# bbb_connection_board.net
KiCad netlist of a schematic drawn in EAGLE
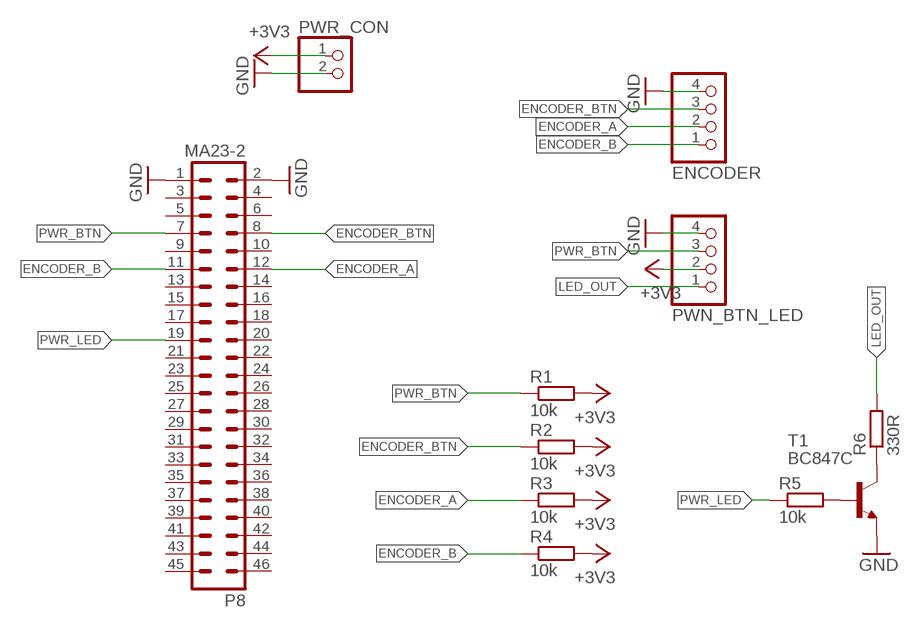
[diagram p0: schematic, sheet 1]

(export (version "E")
  (design (tool "Eeschema 10.0.6"))
  (components
    (comp (ref "ENCODER")
      (value "PINHD-1X4/90")
      (footprint "eagle-import:1X04_90")
      (libsource (lib "eagle-import") (part "PINHD-1X4/90"))
    )
    (comp (ref "P8")
      (value "MA23-2")
      (footprint "eagle-import:MA23-2")
      (libsource (lib "eagle-import") (part "MA23-2"))
    )
    (comp (ref "PWN_BTN_LED")
      (value "PINHD-1X4/90")
      (footprint "eagle-import:1X04_90")
      (libsource (lib "eagle-import") (part "PINHD-1X4/90"))
    )
    (comp (ref "PWR_CON")
      (value "PINHD-1X2/90")
      (footprint "eagle-import:1X02_90")
      (libsource (lib "eagle-import") (part "PINHD-1X2/90"))
    )
    (comp (ref "R1")
      (value "10k")
      (footprint "eagle-import:R0805")
      (libsource (lib "eagle-import") (part "R-EU_R0805"))
    )
    (comp (ref "R2")
      (value "10k")
      (footprint "eagle-import:R0805")
      (libsource (lib "eagle-import") (part "R-EU_R0805"))
    )
    (comp (ref "R3")
      (value "10k")
      (footprint "eagle-import:R0805")
      (libsource (lib "eagle-import") (part "R-EU_R0805"))
    )
    (comp (ref "R4")
      (value "10k")
      (footprint "eagle-import:R0805")
      (libsource (lib "eagle-import") (part "R-EU_R0805"))
    )
    (comp (ref "R5")
      (value "10k")
      (footprint "eagle-import:R0805")
      (libsource (lib "eagle-import") (part "R-EU_R0805"))
    )
    (comp (ref "R6")
      (value "330R")
      (footprint "eagle-import:R0805")
      (libsource (lib "eagle-import") (part "R-EU_R0805"))
    )
    (comp (ref "T1")
      (value "BC847C")
      (footprint "eagle-import:SOT23-BEC")
      (libsource (lib "eagle-import") (part "-NPN-SOT23-BECBC847A"))
    )
  )
  (nets
    (net (code "1") (name "+3V3") (class "Default")
      (node (ref "PWN_BTN_LED") (pin "2") (pinfunction "2_2") (pintype "passive"))
      (node (ref "PWR_CON") (pin "1") (pinfunction "1_1") (pintype "passive"))
      (node (ref "R1") (pin "2") (pinfunction "2_2") (pintype "passive"))
      (node (ref "R2") (pin "2") (pinfunction "2_2") (pintype "passive"))
      (node (ref "R3") (pin "2") (pinfunction "2_2") (pintype "passive"))
      (node (ref "R4") (pin "2") (pinfunction "2_2") (pintype "passive"))
    )
    (net (code "2") (name "ENCODER_A") (class "Default")
      (node (ref "ENCODER") (pin "2") (pinfunction "2_2") (pintype "passive"))
      (node (ref "P8") (pin "12") (pinfunction "12_12") (pintype "passive"))
      (node (ref "R3") (pin "1") (pinfunction "1_1") (pintype "passive"))
    )
    (net (code "3") (name "ENCODER_B") (class "Default")
      (node (ref "ENCODER") (pin "1") (pinfunction "1_1") (pintype "passive"))
      (node (ref "P8") (pin "11") (pinfunction "11_11") (pintype "passive"))
      (node (ref "R4") (pin "1") (pinfunction "1_1") (pintype "passive"))
    )
    (net (code "4") (name "ENCODER_BTN") (class "Default")
      (node (ref "ENCODER") (pin "3") (pinfunction "3_3") (pintype "passive"))
      (node (ref "P8") (pin "8") (pinfunction "8_8") (pintype "passive"))
      (node (ref "R2") (pin "1") (pinfunction "1_1") (pintype "passive"))
    )
    (net (code "5") (name "GND") (class "Default")
      (node (ref "ENCODER") (pin "4") (pinfunction "4_4") (pintype "passive"))
      (node (ref "P8") (pin "1") (pinfunction "1_1") (pintype "passive"))
      (node (ref "P8") (pin "2") (pinfunction "2_2") (pintype "passive"))
      (node (ref "PWN_BTN_LED") (pin "4") (pinfunction "4_4") (pintype "passive"))
      (node (ref "PWR_CON") (pin "2") (pinfunction "2_2") (pintype "passive"))
      (node (ref "T1") (pin "E") (pinfunction "E_E") (pintype "passive"))
    )
    (net (code "6") (name "LED_OUT") (class "Default")
      (node (ref "PWN_BTN_LED") (pin "1") (pinfunction "1_1") (pintype "passive"))
      (node (ref "R6") (pin "2") (pinfunction "2_2") (pintype "passive"))
    )
    (net (code "7") (name "Net-(R5-Pad2)") (class "Default")
      (node (ref "R5") (pin "2") (pinfunction "2_2") (pintype "passive"))
      (node (ref "T1") (pin "B") (pinfunction "B_B") (pintype "passive"))
    )
    (net (code "8") (name "Net-(R6-Pad1)") (class "Default")
      (node (ref "R6") (pin "1") (pinfunction "1_1") (pintype "passive"))
      (node (ref "T1") (pin "C") (pinfunction "C_C") (pintype "passive"))
    )
    (net (code "9") (name "PWR_BTN") (class "Default")
      (node (ref "P8") (pin "7") (pinfunction "7_7") (pintype "passive"))
      (node (ref "PWN_BTN_LED") (pin "3") (pinfunction "3_3") (pintype "passive"))
      (node (ref "R1") (pin "1") (pinfunction "1_1") (pintype "passive"))
    )
    (net (code "10") (name "PWR_LED") (class "Default")
      (node (ref "P8") (pin "19") (pinfunction "19_19") (pintype "passive"))
      (node (ref "R5") (pin "1") (pinfunction "1_1") (pintype "passive"))
    )
    (net (code "11") (name "unconnected-(P8-Pad3)") (class "Default")
      (node (ref "P8") (pin "3") (pinfunction "3_3") (pintype "passive"))
    )
    (net (code "12") (name "unconnected-(P8-Pad4)") (class "Default")
      (node (ref "P8") (pin "4") (pinfunction "4_4") (pintype "passive"))
    )
    (net (code "13") (name "unconnected-(P8-Pad5)") (class "Default")
      (node (ref "P8") (pin "5") (pinfunction "5_5") (pintype "passive"))
    )
    (net (code "14") (name "unconnected-(P8-Pad6)") (class "Default")
      (node (ref "P8") (pin "6") (pinfunction "6_6") (pintype "passive"))
    )
    (net (code "15") (name "unconnected-(P8-Pad9)") (class "Default")
      (node (ref "P8") (pin "9") (pinfunction "9_9") (pintype "passive"))
    )
    (net (code "16") (name "unconnected-(P8-Pad10)") (class "Default")
      (node (ref "P8") (pin "10") (pinfunction "10_10") (pintype "passive"))
    )
    (net (code "17") (name "unconnected-(P8-Pad13)") (class "Default")
      (node (ref "P8") (pin "13") (pinfunction "13_13") (pintype "passive"))
    )
    (net (code "18") (name "unconnected-(P8-Pad14)") (class "Default")
      (node (ref "P8") (pin "14") (pinfunction "14_14") (pintype "passive"))
    )
    (net (code "19") (name "unconnected-(P8-Pad15)") (class "Default")
      (node (ref "P8") (pin "15") (pinfunction "15_15") (pintype "passive"))
    )
    (net (code "20") (name "unconnected-(P8-Pad16)") (class "Default")
      (node (ref "P8") (pin "16") (pinfunction "16_16") (pintype "passive"))
    )
    (net (code "21") (name "unconnected-(P8-Pad17)") (class "Default")
      (node (ref "P8") (pin "17") (pinfunction "17_17") (pintype "passive"))
    )
    (net (code "22") (name "unconnected-(P8-Pad18)") (class "Default")
      (node (ref "P8") (pin "18") (pinfunction "18_18") (pintype "passive"))
    )
    (net (code "23") (name "unconnected-(P8-Pad20)") (class "Default")
      (node (ref "P8") (pin "20") (pinfunction "20_20") (pintype "passive"))
    )
    (net (code "24") (name "unconnected-(P8-Pad21)") (class "Default")
      (node (ref "P8") (pin "21") (pinfunction "21_21") (pintype "passive"))
    )
    (net (code "25") (name "unconnected-(P8-Pad22)") (class "Default")
      (node (ref "P8") (pin "22") (pinfunction "22_22") (pintype "passive"))
    )
    (net (code "26") (name "unconnected-(P8-Pad23)") (class "Default")
      (node (ref "P8") (pin "23") (pinfunction "23_23") (pintype "passive"))
    )
    (net (code "27") (name "unconnected-(P8-Pad24)") (class "Default")
      (node (ref "P8") (pin "24") (pinfunction "24_24") (pintype "passive"))
    )
    (net (code "28") (name "unconnected-(P8-Pad25)") (class "Default")
      (node (ref "P8") (pin "25") (pinfunction "25_25") (pintype "passive"))
    )
    (net (code "29") (name "unconnected-(P8-Pad26)") (class "Default")
      (node (ref "P8") (pin "26") (pinfunction "26_26") (pintype "passive"))
    )
    (net (code "30") (name "unconnected-(P8-Pad27)") (class "Default")
      (node (ref "P8") (pin "27") (pinfunction "27_27") (pintype "passive"))
    )
    (net (code "31") (name "unconnected-(P8-Pad28)") (class "Default")
      (node (ref "P8") (pin "28") (pinfunction "28_28") (pintype "passive"))
    )
    (net (code "32") (name "unconnected-(P8-Pad29)") (class "Default")
      (node (ref "P8") (pin "29") (pinfunction "29_29") (pintype "passive"))
    )
    (net (code "33") (name "unconnected-(P8-Pad30)") (class "Default")
      (node (ref "P8") (pin "30") (pinfunction "30_30") (pintype "passive"))
    )
    (net (code "34") (name "unconnected-(P8-Pad31)") (class "Default")
      (node (ref "P8") (pin "31") (pinfunction "31_31") (pintype "passive"))
    )
    (net (code "35") (name "unconnected-(P8-Pad32)") (class "Default")
      (node (ref "P8") (pin "32") (pinfunction "32_32") (pintype "passive"))
    )
    (net (code "36") (name "unconnected-(P8-Pad33)") (class "Default")
      (node (ref "P8") (pin "33") (pinfunction "33_33") (pintype "passive"))
    )
    (net (code "37") (name "unconnected-(P8-Pad34)") (class "Default")
      (node (ref "P8") (pin "34") (pinfunction "34_34") (pintype "passive"))
    )
    (net (code "38") (name "unconnected-(P8-Pad35)") (class "Default")
      (node (ref "P8") (pin "35") (pinfunction "35_35") (pintype "passive"))
    )
    (net (code "39") (name "unconnected-(P8-Pad36)") (class "Default")
      (node (ref "P8") (pin "36") (pinfunction "36_36") (pintype "passive"))
    )
    (net (code "40") (name "unconnected-(P8-Pad37)") (class "Default")
      (node (ref "P8") (pin "37") (pinfunction "37_37") (pintype "passive"))
    )
    (net (code "41") (name "unconnected-(P8-Pad38)") (class "Default")
      (node (ref "P8") (pin "38") (pinfunction "38_38") (pintype "passive"))
    )
    (net (code "42") (name "unconnected-(P8-Pad39)") (class "Default")
      (node (ref "P8") (pin "39") (pinfunction "39_39") (pintype "passive"))
    )
    (net (code "43") (name "unconnected-(P8-Pad40)") (class "Default")
      (node (ref "P8") (pin "40") (pinfunction "40_40") (pintype "passive"))
    )
    (net (code "44") (name "unconnected-(P8-Pad41)") (class "Default")
      (node (ref "P8") (pin "41") (pinfunction "41_41") (pintype "passive"))
    )
    (net (code "45") (name "unconnected-(P8-Pad42)") (class "Default")
      (node (ref "P8") (pin "42") (pinfunction "42_42") (pintype "passive"))
    )
    (net (code "46") (name "unconnected-(P8-Pad43)") (class "Default")
      (node (ref "P8") (pin "43") (pinfunction "43_43") (pintype "passive"))
    )
    (net (code "47") (name "unconnected-(P8-Pad44)") (class "Default")
      (node (ref "P8") (pin "44") (pinfunction "44_44") (pintype "passive"))
    )
    (net (code "48") (name "unconnected-(P8-Pad45)") (class "Default")
      (node (ref "P8") (pin "45") (pinfunction "45_45") (pintype "passive"))
    )
    (net (code "49") (name "unconnected-(P8-Pad46)") (class "Default")
      (node (ref "P8") (pin "46") (pinfunction "46_46") (pintype "passive"))
    )
  )
)
